# Lab_1.net
KiCad netlist of a schematic drawn in EAGLE
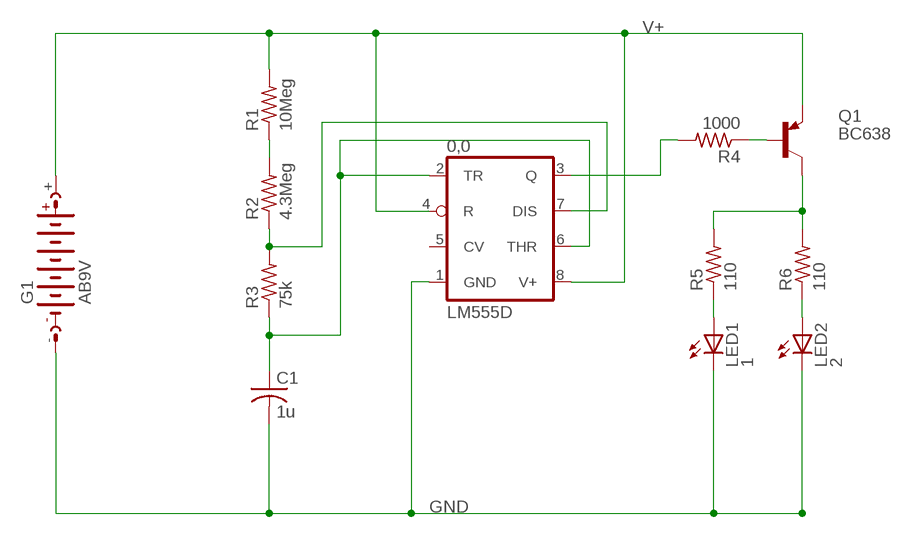
[diagram p0: schematic, sheet 1]

(export (version "E")
  (design (tool "Eeschema 10.0.6"))
  (components
    (comp (ref "0,0")
      (value "LM555D")
      (footprint "eagle-import:SO08")
      (libsource (lib "eagle-import") (part "555DLM"))
    )
    (comp (ref "C1")
      (value "1u")
      (footprint "eagle-import:C1206")
      (libsource (lib "eagle-import") (part "C-USC1206"))
    )
    (comp (ref "G1")
      (value "AB9V")
      (footprint "eagle-import:AB9V")
      (libsource (lib "eagle-import") (part "AB9V"))
    )
    (comp (ref "LED1")
      (value "1")
      (footprint "eagle-import:LED3MM")
      (libsource (lib "eagle-import") (part "LED3MM"))
    )
    (comp (ref "LED2")
      (value "2")
      (footprint "eagle-import:LED3MM")
      (libsource (lib "eagle-import") (part "LED3MM"))
    )
    (comp (ref "Q1")
      (value "BC638")
      (footprint "eagle-import:TO92-BCE")
      (libsource (lib "eagle-import") (part "BC638"))
    )
    (comp (ref "R1")
      (value "10Meg")
      (footprint "eagle-import:M0805")
      (libsource (lib "eagle-import") (part "R-US_M0805"))
    )
    (comp (ref "R2")
      (value "4.3Meg")
      (footprint "eagle-import:M0805")
      (libsource (lib "eagle-import") (part "R-US_M0805"))
    )
    (comp (ref "R3")
      (value "75k")
      (footprint "eagle-import:M0805")
      (libsource (lib "eagle-import") (part "R-US_M0805"))
    )
    (comp (ref "R4")
      (value "1000")
      (footprint "eagle-import:M0805")
      (libsource (lib "eagle-import") (part "R-US_M0805"))
    )
    (comp (ref "R5")
      (value "110")
      (footprint "eagle-import:M0805")
      (libsource (lib "eagle-import") (part "R-US_M0805"))
    )
    (comp (ref "R6")
      (value "110")
      (footprint "eagle-import:M0805")
      (libsource (lib "eagle-import") (part "R-US_M0805"))
    )
  )
  (nets
    (net (code "1") (name "/GND") (class "Default")
      (node (ref "0,0") (pin "1") (pinfunction "GND_1") (pintype "power_in"))
      (node (ref "C1") (pin "2") (pinfunction "2_2") (pintype "passive"))
      (node (ref "G1") (pin "-") (pinfunction "-_-") (pintype "passive"))
      (node (ref "LED1") (pin "K") (pinfunction "C_K") (pintype "passive"))
      (node (ref "LED2") (pin "K") (pinfunction "C_K") (pintype "passive"))
    )
    (net (code "2") (name "/V+") (class "Default")
      (node (ref "0,0") (pin "4") (pinfunction "R_4") (pintype "input"))
      (node (ref "0,0") (pin "8") (pinfunction "V+_8") (pintype "power_in"))
      (node (ref "G1") (pin "+") (pinfunction "+_+") (pintype "passive"))
      (node (ref "Q1") (pin "E") (pinfunction "E_E") (pintype "passive"))
      (node (ref "R1") (pin "2") (pinfunction "2_2") (pintype "passive"))
    )
    (net (code "3") (name "Net-(0,0-DIS)") (class "Default")
      (node (ref "0,0") (pin "7") (pinfunction "DIS_7") (pintype "input"))
      (node (ref "R2") (pin "1") (pinfunction "1_1") (pintype "passive"))
      (node (ref "R3") (pin "2") (pinfunction "2_2") (pintype "passive"))
    )
    (net (code "4") (name "Net-(0,0-Q)") (class "Default")
      (node (ref "0,0") (pin "3") (pinfunction "Q_3") (pintype "output"))
      (node (ref "R4") (pin "2") (pinfunction "2_2") (pintype "passive"))
    )
    (net (code "5") (name "Net-(0,0-THR)") (class "Default")
      (node (ref "0,0") (pin "2") (pinfunction "TR_2") (pintype "input"))
      (node (ref "0,0") (pin "6") (pinfunction "THR_6") (pintype "input"))
      (node (ref "C1") (pin "1") (pinfunction "1_1") (pintype "passive"))
      (node (ref "R3") (pin "1") (pinfunction "1_1") (pintype "passive"))
    )
    (net (code "6") (name "Net-(LED1-PadA)") (class "Default")
      (node (ref "LED1") (pin "A") (pinfunction "A_A") (pintype "passive"))
      (node (ref "R5") (pin "1") (pinfunction "1_1") (pintype "passive"))
    )
    (net (code "7") (name "Net-(LED2-PadA)") (class "Default")
      (node (ref "LED2") (pin "A") (pinfunction "A_A") (pintype "passive"))
      (node (ref "R6") (pin "1") (pinfunction "1_1") (pintype "passive"))
    )
    (net (code "8") (name "Net-(Q1-PadB)") (class "Default")
      (node (ref "Q1") (pin "B") (pinfunction "B_B") (pintype "passive"))
      (node (ref "R4") (pin "1") (pinfunction "1_1") (pintype "passive"))
    )
    (net (code "9") (name "Net-(Q1-PadC)") (class "Default")
      (node (ref "Q1") (pin "C") (pinfunction "C_C") (pintype "passive"))
      (node (ref "R5") (pin "2") (pinfunction "2_2") (pintype "passive"))
      (node (ref "R6") (pin "2") (pinfunction "2_2") (pintype "passive"))
    )
    (net (code "10") (name "Net-(R1-Pad1)") (class "Default")
      (node (ref "R1") (pin "1") (pinfunction "1_1") (pintype "passive"))
      (node (ref "R2") (pin "2") (pinfunction "2_2") (pintype "passive"))
    )
    (net (code "11") (name "unconnected-(0,0-CV-Pad5)") (class "Default")
      (node (ref "0,0") (pin "5") (pinfunction "CV_5") (pintype "input"))
    )
  )
)
